# MPU9250.net
KiCad netlist of a schematic drawn in Altium Designer
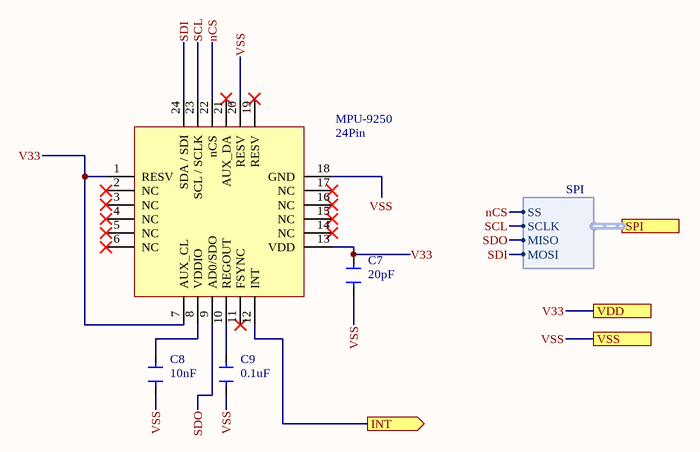
[diagram p0: MPU9250.SchDoc]

(export (version "E")
  (design (tool "Eeschema 10.0.6"))
  (components
    (comp (ref "C7")
      (value "20pF")
      (footprint "CAP_0402")
      (fields (field (name "Comment") "Cap"))
      (libsource (lib "ZGR") (part "Cap"))
    )
    (comp (ref "C8")
      (value "10nF")
      (footprint "CAP_0402")
      (fields (field (name "Comment") "Cap"))
      (libsource (lib "ZGR") (part "Cap"))
    )
    (comp (ref "C9")
      (value "0.1uF")
      (footprint "CAP_0402")
      (fields (field (name "Comment") "Cap"))
      (libsource (lib "ZGR") (part "Cap"))
    )
    (comp (ref "MPU-9250")
      (value "24Pin")
      (footprint "QFN_24PIN")
      (libsource (lib "ZGR") (part "MPU-9250_2"))
    )
  )
  (nets
    (net (code "2") (name "/INT") (class "Default")
      (node (ref "MPU-9250") (pin "12") (pinfunction "INT_12") (pintype "passive"))
    )
    (net (code "3") (name "/SCL") (class "Default")
      (node (ref "MPU-9250") (pin "23") (pinfunction "SCL_/_SCLK_23") (pintype "passive"))
    )
    (net (code "4") (name "/SDI") (class "Default")
      (node (ref "MPU-9250") (pin "24") (pinfunction "SDA_/_SDI_24") (pintype "passive"))
    )
    (net (code "5") (name "/SDO") (class "Default")
      (node (ref "MPU-9250") (pin "9") (pinfunction "AD0/SDO_9") (pintype "passive"))
    )
    (net (code "6") (name "/V33") (class "Default")
      (node (ref "C7") (pin "1") (pinfunction "1_1") (pintype "passive"))
      (node (ref "MPU-9250") (pin "1") (pinfunction "RESV_1") (pintype "passive"))
      (node (ref "MPU-9250") (pin "13") (pinfunction "VDD_13") (pintype "passive"))
      (node (ref "MPU-9250") (pin "7") (pinfunction "AUX_CL_7") (pintype "passive"))
    )
    (net (code "7") (name "/VSS") (class "Default")
      (node (ref "C7") (pin "2") (pinfunction "2_2") (pintype "passive"))
      (node (ref "C8") (pin "2") (pinfunction "2_2") (pintype "passive"))
      (node (ref "C9") (pin "2") (pinfunction "2_2") (pintype "passive"))
      (node (ref "MPU-9250") (pin "18") (pinfunction "GND_18") (pintype "passive"))
      (node (ref "MPU-9250") (pin "20") (pinfunction "RESV_20") (pintype "passive"))
    )
    (net (code "8") (name "/nCS") (class "Default")
      (node (ref "MPU-9250") (pin "22") (pinfunction "nCS_22") (pintype "passive"))
    )
    (net (code "10") (name "Net-(MPU-9250-REGOUT)") (class "Default")
      (node (ref "C9") (pin "1") (pinfunction "1_1") (pintype "passive"))
      (node (ref "MPU-9250") (pin "10") (pinfunction "REGOUT_10") (pintype "passive"))
    )
    (net (code "11") (name "Net-(MPU-9250-VDDIO)") (class "Default")
      (node (ref "C8") (pin "1") (pinfunction "1_1") (pintype "passive"))
      (node (ref "MPU-9250") (pin "8") (pinfunction "VDDIO_8") (pintype "passive"))
    )
    (net (code "12") (name "unconnected-(MPU-9250-AUX_DA-Pad21)") (class "Default")
      (node (ref "MPU-9250") (pin "21") (pinfunction "AUX_DA_21") (pintype "passive+no_connect"))
    )
    (net (code "13") (name "unconnected-(MPU-9250-FSYNC-Pad11)") (class "Default")
      (node (ref "MPU-9250") (pin "11") (pinfunction "FSYNC_11") (pintype "passive+no_connect"))
    )
    (net (code "14") (name "unconnected-(MPU-9250-NC-Pad2)") (class "Default")
      (node (ref "MPU-9250") (pin "2") (pinfunction "NC_2") (pintype "passive+no_connect"))
    )
    (net (code "15") (name "unconnected-(MPU-9250-NC-Pad3)") (class "Default")
      (node (ref "MPU-9250") (pin "3") (pinfunction "NC_3") (pintype "passive+no_connect"))
    )
    (net (code "16") (name "unconnected-(MPU-9250-NC-Pad4)") (class "Default")
      (node (ref "MPU-9250") (pin "4") (pinfunction "NC_4") (pintype "passive+no_connect"))
    )
    (net (code "17") (name "unconnected-(MPU-9250-NC-Pad5)") (class "Default")
      (node (ref "MPU-9250") (pin "5") (pinfunction "NC_5") (pintype "passive+no_connect"))
    )
    (net (code "18") (name "unconnected-(MPU-9250-NC-Pad6)") (class "Default")
      (node (ref "MPU-9250") (pin "6") (pinfunction "NC_6") (pintype "passive+no_connect"))
    )
    (net (code "19") (name "unconnected-(MPU-9250-NC-Pad14)") (class "Default")
      (node (ref "MPU-9250") (pin "14") (pinfunction "NC_14") (pintype "passive+no_connect"))
    )
    (net (code "20") (name "unconnected-(MPU-9250-NC-Pad15)") (class "Default")
      (node (ref "MPU-9250") (pin "15") (pinfunction "NC_15") (pintype "passive+no_connect"))
    )
    (net (code "21") (name "unconnected-(MPU-9250-NC-Pad16)") (class "Default")
      (node (ref "MPU-9250") (pin "16") (pinfunction "NC_16") (pintype "passive+no_connect"))
    )
    (net (code "22") (name "unconnected-(MPU-9250-NC-Pad17)") (class "Default")
      (node (ref "MPU-9250") (pin "17") (pinfunction "NC_17") (pintype "passive+no_connect"))
    )
    (net (code "23") (name "unconnected-(MPU-9250-RESV-Pad19)") (class "Default")
      (node (ref "MPU-9250") (pin "19") (pinfunction "RESV_19") (pintype "passive+no_connect"))
    )
  )
)
